# 3_3_5_9_12.net
KiCad netlist of a schematic drawn in EAGLE
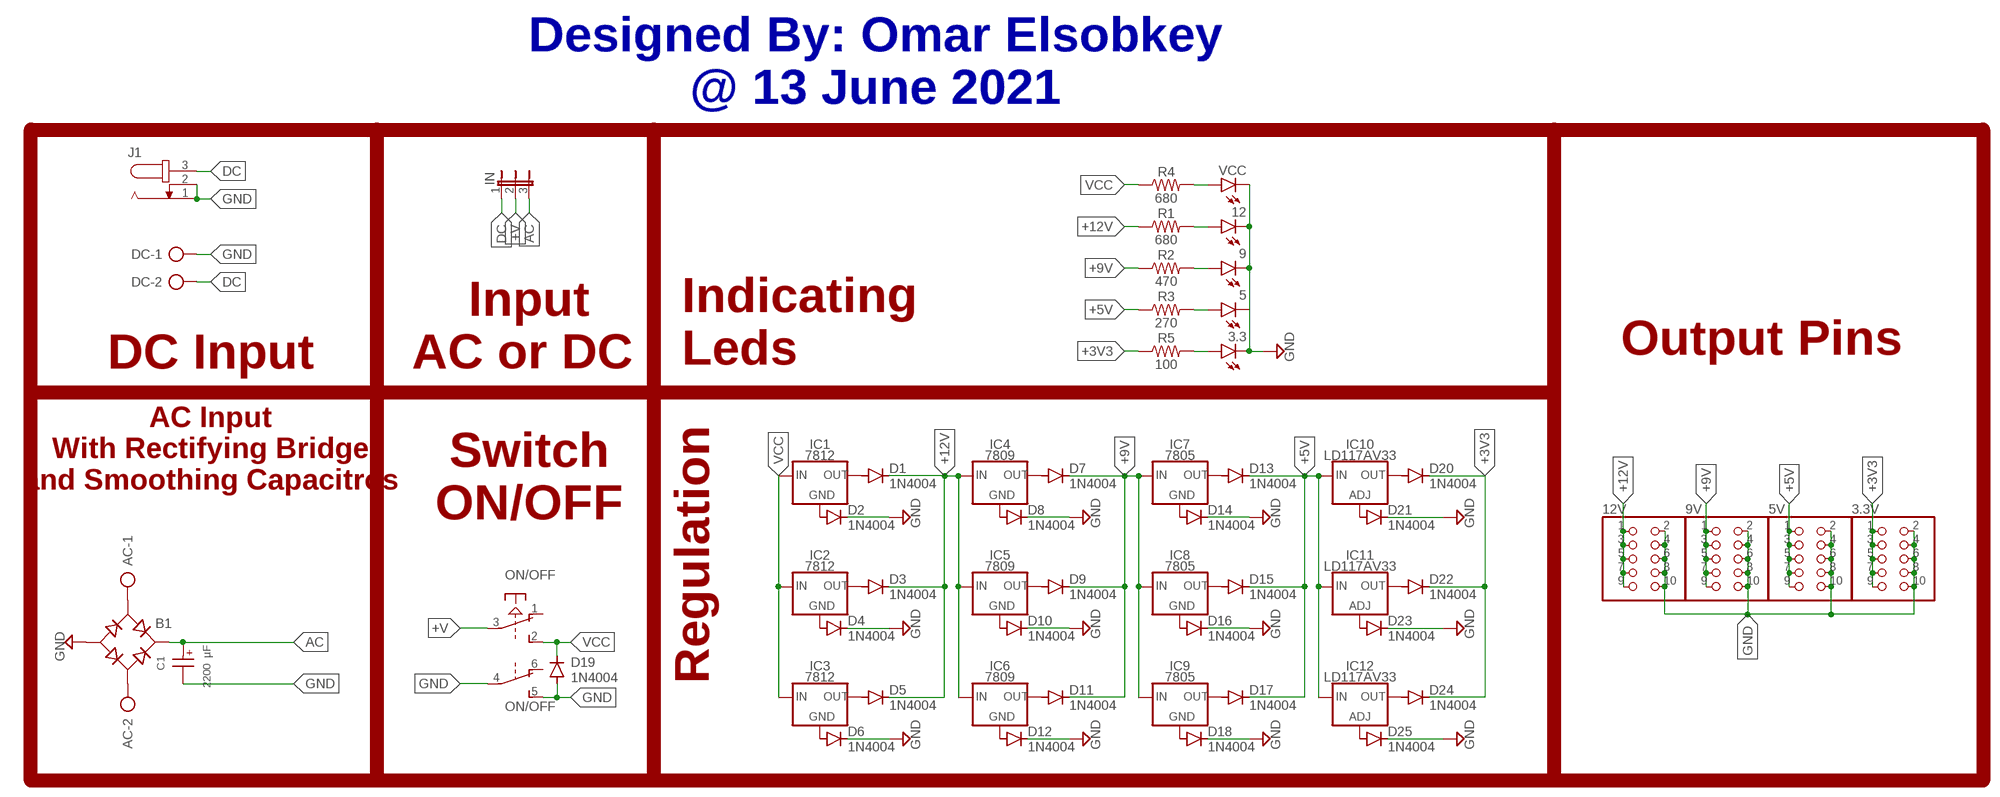
[diagram p0: schematic, sheet 1]

(export (version "E")
  (design (tool "Eeschema 10.0.6"))
  (components
    (comp (ref "3.3")
      (value "LED5MM")
      (footprint "eagle-import:LED5MM")
      (libsource (lib "eagle-import") (part "LED5MM"))
    )
    (comp (ref "3.3V")
      (value "PINHD-2X5")
      (footprint "eagle-import:2X05")
      (libsource (lib "eagle-import") (part "PINHD-2X5"))
    )
    (comp (ref "5")
      (value "LED5MM")
      (footprint "eagle-import:LED5MM")
      (libsource (lib "eagle-import") (part "LED5MM"))
    )
    (comp (ref "5V")
      (value "PINHD-2X5")
      (footprint "eagle-import:2X05")
      (libsource (lib "eagle-import") (part "PINHD-2X5"))
    )
    (comp (ref "9")
      (value "LED5MM")
      (footprint "eagle-import:LED5MM")
      (libsource (lib "eagle-import") (part "LED5MM"))
    )
    (comp (ref "9V")
      (value "PINHD-2X5")
      (footprint "eagle-import:2X05")
      (libsource (lib "eagle-import") (part "PINHD-2X5"))
    )
    (comp (ref "12")
      (value "LED5MM")
      (footprint "eagle-import:LED5MM")
      (libsource (lib "eagle-import") (part "LED5MM"))
    )
    (comp (ref "12V")
      (value "PINHD-2X5")
      (footprint "eagle-import:2X05")
      (libsource (lib "eagle-import") (part "PINHD-2X5"))
    )
    (comp (ref "AC")
      (value "AK500/2-H")
      (footprint "eagle-import:AK500_2-H")
      (libsource (lib "eagle-import") (part "AK500/2-H"))
    )
    (comp (ref "B1")
      (value "RB1A")
      (footprint "eagle-import:RB1A")
      (libsource (lib "eagle-import") (part "RB1A"))
    )
    (comp (ref "C1")
      (value "2200 µF")
      (footprint "eagle-import:WCAP-ATG8_16X25(DXL)")
      (libsource (lib "eagle-import") (part "WCAP-ATG8_16X25_860010580021"))
    )
    (comp (ref "D1")
      (value "1N4004")
      (footprint "eagle-import:DO41-10")
      (libsource (lib "eagle-import") (part "1N4004"))
    )
    (comp (ref "D2")
      (value "1N4004")
      (footprint "eagle-import:DO41-10")
      (libsource (lib "eagle-import") (part "1N4004"))
    )
    (comp (ref "D3")
      (value "1N4004")
      (footprint "eagle-import:DO41-10")
      (libsource (lib "eagle-import") (part "1N4004"))
    )
    (comp (ref "D4")
      (value "1N4004")
      (footprint "eagle-import:DO41-10")
      (libsource (lib "eagle-import") (part "1N4004"))
    )
    (comp (ref "D5")
      (value "1N4004")
      (footprint "eagle-import:DO41-10")
      (libsource (lib "eagle-import") (part "1N4004"))
    )
    (comp (ref "D6")
      (value "1N4004")
      (footprint "eagle-import:DO41-10")
      (libsource (lib "eagle-import") (part "1N4004"))
    )
    (comp (ref "D7")
      (value "1N4004")
      (footprint "eagle-import:DO41-10")
      (libsource (lib "eagle-import") (part "1N4004"))
    )
    (comp (ref "D8")
      (value "1N4004")
      (footprint "eagle-import:DO41-10")
      (libsource (lib "eagle-import") (part "1N4004"))
    )
    (comp (ref "D9")
      (value "1N4004")
      (footprint "eagle-import:DO41-10")
      (libsource (lib "eagle-import") (part "1N4004"))
    )
    (comp (ref "D10")
      (value "1N4004")
      (footprint "eagle-import:DO41-10")
      (libsource (lib "eagle-import") (part "1N4004"))
    )
    (comp (ref "D11")
      (value "1N4004")
      (footprint "eagle-import:DO41-10")
      (libsource (lib "eagle-import") (part "1N4004"))
    )
    (comp (ref "D12")
      (value "1N4004")
      (footprint "eagle-import:DO41-10")
      (libsource (lib "eagle-import") (part "1N4004"))
    )
    (comp (ref "D13")
      (value "1N4004")
      (footprint "eagle-import:DO41-10")
      (libsource (lib "eagle-import") (part "1N4004"))
    )
    (comp (ref "D14")
      (value "1N4004")
      (footprint "eagle-import:DO41-10")
      (libsource (lib "eagle-import") (part "1N4004"))
    )
    (comp (ref "D15")
      (value "1N4004")
      (footprint "eagle-import:DO41-10")
      (libsource (lib "eagle-import") (part "1N4004"))
    )
    (comp (ref "D16")
      (value "1N4004")
      (footprint "eagle-import:DO41-10")
      (libsource (lib "eagle-import") (part "1N4004"))
    )
    (comp (ref "D17")
      (value "1N4004")
      (footprint "eagle-import:DO41-10")
      (libsource (lib "eagle-import") (part "1N4004"))
    )
    (comp (ref "D18")
      (value "1N4004")
      (footprint "eagle-import:DO41-10")
      (libsource (lib "eagle-import") (part "1N4004"))
    )
    (comp (ref "D19")
      (value "1N4004")
      (footprint "eagle-import:DO41-10")
      (libsource (lib "eagle-import") (part "1N4004"))
    )
    (comp (ref "D20")
      (value "1N4004")
      (footprint "eagle-import:DO41-10")
      (libsource (lib "eagle-import") (part "1N4004"))
    )
    (comp (ref "D21")
      (value "1N4004")
      (footprint "eagle-import:DO41-10")
      (libsource (lib "eagle-import") (part "1N4004"))
    )
    (comp (ref "D22")
      (value "1N4004")
      (footprint "eagle-import:DO41-10")
      (libsource (lib "eagle-import") (part "1N4004"))
    )
    (comp (ref "D23")
      (value "1N4004")
      (footprint "eagle-import:DO41-10")
      (libsource (lib "eagle-import") (part "1N4004"))
    )
    (comp (ref "D24")
      (value "1N4004")
      (footprint "eagle-import:DO41-10")
      (libsource (lib "eagle-import") (part "1N4004"))
    )
    (comp (ref "D25")
      (value "1N4004")
      (footprint "eagle-import:DO41-10")
      (libsource (lib "eagle-import") (part "1N4004"))
    )
    (comp (ref "DC")
      (value "AK500/2-H")
      (footprint "eagle-import:AK500_2-H")
      (libsource (lib "eagle-import") (part "AK500/2-H"))
    )
    (comp (ref "IC1")
      (value "7812")
      (footprint "eagle-import:78XXS")
      (libsource (lib "eagle-import") (part "78XXS"))
    )
    (comp (ref "IC2")
      (value "7812")
      (footprint "eagle-import:78XXS")
      (libsource (lib "eagle-import") (part "78XXS"))
    )
    (comp (ref "IC3")
      (value "7812")
      (footprint "eagle-import:78XXS")
      (libsource (lib "eagle-import") (part "78XXS"))
    )
    (comp (ref "IC4")
      (value "7809")
      (footprint "eagle-import:78XXS")
      (libsource (lib "eagle-import") (part "78XXS"))
    )
    (comp (ref "IC5")
      (value "7809")
      (footprint "eagle-import:78XXS")
      (libsource (lib "eagle-import") (part "78XXS"))
    )
    (comp (ref "IC6")
      (value "7809")
      (footprint "eagle-import:78XXS")
      (libsource (lib "eagle-import") (part "78XXS"))
    )
    (comp (ref "IC7")
      (value "7805")
      (footprint "eagle-import:78XXS")
      (libsource (lib "eagle-import") (part "78XXS"))
    )
    (comp (ref "IC8")
      (value "7805")
      (footprint "eagle-import:78XXS")
      (libsource (lib "eagle-import") (part "78XXS"))
    )
    (comp (ref "IC9")
      (value "7805")
      (footprint "eagle-import:78XXS")
      (libsource (lib "eagle-import") (part "78XXS"))
    )
    (comp (ref "IC10")
      (value "LD117AV33")
      (footprint "eagle-import:TO220L1")
      (libsource (lib "eagle-import") (part "LD117A?V33"))
    )
    (comp (ref "IC11")
      (value "LD117AV33")
      (footprint "eagle-import:TO220L1")
      (libsource (lib "eagle-import") (part "LD117A?V33"))
    )
    (comp (ref "IC12")
      (value "LD117AV33")
      (footprint "eagle-import:TO220L1")
      (libsource (lib "eagle-import") (part "LD117A?V33"))
    )
    (comp (ref "IN")
      (value "JP2E")
      (footprint "eagle-import:JP2")
      (libsource (lib "eagle-import") (part "JP2E"))
    )
    (comp (ref "J1")
      (value "JACK-PLUG0")
      (footprint "eagle-import:SPC4077")
      (libsource (lib "eagle-import") (part "JACK-PLUG0"))
    )
    (comp (ref "ON/OFF")
      (value "PVA2R")
      (footprint "eagle-import:PVA2R")
      (libsource (lib "eagle-import") (part "PVA2R"))
    )
    (comp (ref "R1")
      (value "680")
      (footprint "eagle-import:AXIAL-0.3")
      (libsource (lib "eagle-import") (part "RESISTORAXIAL-0.3"))
    )
    (comp (ref "R2")
      (value "470")
      (footprint "eagle-import:AXIAL-0.3")
      (libsource (lib "eagle-import") (part "RESISTORAXIAL-0.3"))
    )
    (comp (ref "R3")
      (value "270")
      (footprint "eagle-import:AXIAL-0.3")
      (libsource (lib "eagle-import") (part "RESISTORAXIAL-0.3"))
    )
    (comp (ref "R4")
      (value "680")
      (footprint "eagle-import:AXIAL-0.3")
      (libsource (lib "eagle-import") (part "RESISTORAXIAL-0.3"))
    )
    (comp (ref "R5")
      (value "100")
      (footprint "eagle-import:AXIAL-0.3")
      (libsource (lib "eagle-import") (part "RESISTORAXIAL-0.3"))
    )
    (comp (ref "VCC")
      (value "LED5MM")
      (footprint "eagle-import:LED5MM")
      (libsource (lib "eagle-import") (part "LED5MM"))
    )
  )
  (nets
    (net (code "1") (name "+3V3") (class "Default")
      (node (ref "3.3V") (pin "1") (pinfunction "1_1") (pintype "passive"))
      (node (ref "3.3V") (pin "3") (pinfunction "3_3") (pintype "passive"))
      (node (ref "3.3V") (pin "5") (pinfunction "5_5") (pintype "passive"))
      (node (ref "3.3V") (pin "7") (pinfunction "7_7") (pintype "passive"))
      (node (ref "3.3V") (pin "9") (pinfunction "9_9") (pintype "passive"))
      (node (ref "D20") (pin "C") (pinfunction "C_C") (pintype "passive"))
      (node (ref "D22") (pin "C") (pinfunction "C_C") (pintype "passive"))
      (node (ref "D24") (pin "C") (pinfunction "C_C") (pintype "passive"))
      (node (ref "R5") (pin "P$1") (pinfunction "1_P$1") (pintype "passive"))
    )
    (net (code "2") (name "+5V") (class "Default")
      (node (ref "5V") (pin "1") (pinfunction "1_1") (pintype "passive"))
      (node (ref "5V") (pin "3") (pinfunction "3_3") (pintype "passive"))
      (node (ref "5V") (pin "5") (pinfunction "5_5") (pintype "passive"))
      (node (ref "5V") (pin "7") (pinfunction "7_7") (pintype "passive"))
      (node (ref "5V") (pin "9") (pinfunction "9_9") (pintype "passive"))
      (node (ref "D13") (pin "C") (pinfunction "C_C") (pintype "passive"))
      (node (ref "D15") (pin "C") (pinfunction "C_C") (pintype "passive"))
      (node (ref "D17") (pin "C") (pinfunction "C_C") (pintype "passive"))
      (node (ref "IC10") (pin "3") (pinfunction "IN_3") (pintype "input"))
      (node (ref "IC11") (pin "3") (pinfunction "IN_3") (pintype "input"))
      (node (ref "IC12") (pin "3") (pinfunction "IN_3") (pintype "input"))
      (node (ref "R3") (pin "P$1") (pinfunction "1_P$1") (pintype "passive"))
    )
    (net (code "3") (name "+9V") (class "Default")
      (node (ref "9V") (pin "1") (pinfunction "1_1") (pintype "passive"))
      (node (ref "9V") (pin "3") (pinfunction "3_3") (pintype "passive"))
      (node (ref "9V") (pin "5") (pinfunction "5_5") (pintype "passive"))
      (node (ref "9V") (pin "7") (pinfunction "7_7") (pintype "passive"))
      (node (ref "9V") (pin "9") (pinfunction "9_9") (pintype "passive"))
      (node (ref "D11") (pin "C") (pinfunction "C_C") (pintype "passive"))
      (node (ref "D7") (pin "C") (pinfunction "C_C") (pintype "passive"))
      (node (ref "D9") (pin "C") (pinfunction "C_C") (pintype "passive"))
      (node (ref "IC7") (pin "IN") (pinfunction "IN_IN") (pintype "input"))
      (node (ref "IC8") (pin "IN") (pinfunction "IN_IN") (pintype "input"))
      (node (ref "IC9") (pin "IN") (pinfunction "IN_IN") (pintype "input"))
      (node (ref "R2") (pin "P$1") (pinfunction "1_P$1") (pintype "passive"))
    )
    (net (code "4") (name "+12V") (class "Default")
      (node (ref "12V") (pin "1") (pinfunction "1_1") (pintype "passive"))
      (node (ref "12V") (pin "3") (pinfunction "3_3") (pintype "passive"))
      (node (ref "12V") (pin "5") (pinfunction "5_5") (pintype "passive"))
      (node (ref "12V") (pin "7") (pinfunction "7_7") (pintype "passive"))
      (node (ref "12V") (pin "9") (pinfunction "9_9") (pintype "passive"))
      (node (ref "D1") (pin "C") (pinfunction "C_C") (pintype "passive"))
      (node (ref "D3") (pin "C") (pinfunction "C_C") (pintype "passive"))
      (node (ref "D5") (pin "C") (pinfunction "C_C") (pintype "passive"))
      (node (ref "IC4") (pin "IN") (pinfunction "IN_IN") (pintype "input"))
      (node (ref "IC5") (pin "IN") (pinfunction "IN_IN") (pintype "input"))
      (node (ref "IC6") (pin "IN") (pinfunction "IN_IN") (pintype "input"))
      (node (ref "R1") (pin "P$1") (pinfunction "1_P$1") (pintype "passive"))
    )
    (net (code "5") (name "+V") (class "Default")
      (node (ref "IN") (pin "2") (pinfunction "2_2") (pintype "passive"))
      (node (ref "ON/OFF") (pin "3") (pinfunction "P_3") (pintype "passive"))
    )
    (net (code "6") (name "AC") (class "Default")
      (node (ref "B1") (pin "+") (pinfunction "+_+") (pintype "passive"))
      (node (ref "C1") (pin "1") (pinfunction "+_1") (pintype "passive"))
      (node (ref "IN") (pin "3") (pinfunction "3_3") (pintype "passive"))
    )
    (net (code "7") (name "DC") (class "Default")
      (node (ref "DC") (pin "2") (pinfunction "KL_2") (pintype "passive"))
      (node (ref "IN") (pin "1") (pinfunction "1_1") (pintype "passive"))
      (node (ref "J1") (pin "3") (pinfunction "3_3") (pintype "passive"))
    )
    (net (code "8") (name "GND") (class "Default")
      (node (ref "12") (pin "K") (pinfunction "C_K") (pintype "passive"))
      (node (ref "12V") (pin "10") (pinfunction "10_10") (pintype "passive"))
      (node (ref "12V") (pin "2") (pinfunction "2_2") (pintype "passive"))
      (node (ref "12V") (pin "4") (pinfunction "4_4") (pintype "passive"))
      (node (ref "12V") (pin "6") (pinfunction "6_6") (pintype "passive"))
      (node (ref "12V") (pin "8") (pinfunction "8_8") (pintype "passive"))
      (node (ref "3.3") (pin "K") (pinfunction "C_K") (pintype "passive"))
      (node (ref "3.3V") (pin "10") (pinfunction "10_10") (pintype "passive"))
      (node (ref "3.3V") (pin "2") (pinfunction "2_2") (pintype "passive"))
      (node (ref "3.3V") (pin "4") (pinfunction "4_4") (pintype "passive"))
      (node (ref "3.3V") (pin "6") (pinfunction "6_6") (pintype "passive"))
      (node (ref "3.3V") (pin "8") (pinfunction "8_8") (pintype "passive"))
      (node (ref "5") (pin "K") (pinfunction "C_K") (pintype "passive"))
      (node (ref "5V") (pin "10") (pinfunction "10_10") (pintype "passive"))
      (node (ref "5V") (pin "2") (pinfunction "2_2") (pintype "passive"))
      (node (ref "5V") (pin "4") (pinfunction "4_4") (pintype "passive"))
      (node (ref "5V") (pin "6") (pinfunction "6_6") (pintype "passive"))
      (node (ref "5V") (pin "8") (pinfunction "8_8") (pintype "passive"))
      (node (ref "9") (pin "K") (pinfunction "C_K") (pintype "passive"))
      (node (ref "9V") (pin "10") (pinfunction "10_10") (pintype "passive"))
      (node (ref "9V") (pin "2") (pinfunction "2_2") (pintype "passive"))
      (node (ref "9V") (pin "4") (pinfunction "4_4") (pintype "passive"))
      (node (ref "9V") (pin "6") (pinfunction "6_6") (pintype "passive"))
      (node (ref "9V") (pin "8") (pinfunction "8_8") (pintype "passive"))
      (node (ref "B1") (pin "-") (pinfunction "-_-") (pintype "passive"))
      (node (ref "C1") (pin "2") (pinfunction "-_2") (pintype "passive"))
      (node (ref "D10") (pin "C") (pinfunction "C_C") (pintype "passive"))
      (node (ref "D12") (pin "C") (pinfunction "C_C") (pintype "passive"))
      (node (ref "D14") (pin "C") (pinfunction "C_C") (pintype "passive"))
      (node (ref "D16") (pin "C") (pinfunction "C_C") (pintype "passive"))
      (node (ref "D18") (pin "C") (pinfunction "C_C") (pintype "passive"))
      (node (ref "D19") (pin "A") (pinfunction "A_A") (pintype "passive"))
      (node (ref "D2") (pin "C") (pinfunction "C_C") (pintype "passive"))
      (node (ref "D21") (pin "C") (pinfunction "C_C") (pintype "passive"))
      (node (ref "D23") (pin "C") (pinfunction "C_C") (pintype "passive"))
      (node (ref "D25") (pin "C") (pinfunction "C_C") (pintype "passive"))
      (node (ref "D4") (pin "C") (pinfunction "C_C") (pintype "passive"))
      (node (ref "D6") (pin "C") (pinfunction "C_C") (pintype "passive"))
      (node (ref "D8") (pin "C") (pinfunction "C_C") (pintype "passive"))
      (node (ref "DC") (pin "1") (pinfunction "KL_1") (pintype "passive"))
      (node (ref "J1") (pin "1") (pinfunction "1_1") (pintype "passive"))
      (node (ref "J1") (pin "2") (pinfunction "2_2") (pintype "passive"))
      (node (ref "ON/OFF") (pin "4") (pinfunction "P_4") (pintype "passive"))
      (node (ref "ON/OFF") (pin "5") (pinfunction "S_5") (pintype "passive"))
      (node (ref "VCC") (pin "K") (pinfunction "C_K") (pintype "passive"))
    )
    (net (code "9") (name "Net-(ACA-KL)") (class "Default")
      (node (ref "AC") (pin "1") (pinfunction "KL_1") (pintype "passive"))
      (node (ref "B1") (pin "AC1") (pinfunction "AC1_AC1") (pintype "passive"))
    )
    (net (code "10") (name "Net-(ACB-KL)") (class "Default")
      (node (ref "AC") (pin "2") (pinfunction "KL_2") (pintype "passive"))
      (node (ref "B1") (pin "AC2") (pinfunction "AC2_AC2") (pintype "passive"))
    )
    (net (code "11") (name "Net-(D1-PadA)") (class "Default")
      (node (ref "D1") (pin "A") (pinfunction "A_A") (pintype "passive"))
      (node (ref "IC1") (pin "OUT") (pinfunction "OUT_OUT") (pintype "passive"))
    )
    (net (code "12") (name "Net-(D2-PadA)") (class "Default")
      (node (ref "D2") (pin "A") (pinfunction "A_A") (pintype "passive"))
      (node (ref "IC1") (pin "GND") (pinfunction "GND_GND") (pintype "input"))
    )
    (net (code "13") (name "Net-(D3-PadA)") (class "Default")
      (node (ref "D3") (pin "A") (pinfunction "A_A") (pintype "passive"))
      (node (ref "IC2") (pin "OUT") (pinfunction "OUT_OUT") (pintype "passive"))
    )
    (net (code "14") (name "Net-(D4-PadA)") (class "Default")
      (node (ref "D4") (pin "A") (pinfunction "A_A") (pintype "passive"))
      (node (ref "IC2") (pin "GND") (pinfunction "GND_GND") (pintype "input"))
    )
    (net (code "15") (name "Net-(D5-PadA)") (class "Default")
      (node (ref "D5") (pin "A") (pinfunction "A_A") (pintype "passive"))
      (node (ref "IC3") (pin "OUT") (pinfunction "OUT_OUT") (pintype "passive"))
    )
    (net (code "16") (name "Net-(D6-PadA)") (class "Default")
      (node (ref "D6") (pin "A") (pinfunction "A_A") (pintype "passive"))
      (node (ref "IC3") (pin "GND") (pinfunction "GND_GND") (pintype "input"))
    )
    (net (code "17") (name "Net-(D7-PadA)") (class "Default")
      (node (ref "D7") (pin "A") (pinfunction "A_A") (pintype "passive"))
      (node (ref "IC4") (pin "OUT") (pinfunction "OUT_OUT") (pintype "passive"))
    )
    (net (code "18") (name "Net-(D8-PadA)") (class "Default")
      (node (ref "D8") (pin "A") (pinfunction "A_A") (pintype "passive"))
      (node (ref "IC4") (pin "GND") (pinfunction "GND_GND") (pintype "input"))
    )
    (net (code "19") (name "Net-(D9-PadA)") (class "Default")
      (node (ref "D9") (pin "A") (pinfunction "A_A") (pintype "passive"))
      (node (ref "IC5") (pin "OUT") (pinfunction "OUT_OUT") (pintype "passive"))
    )
    (net (code "20") (name "Net-(D10-PadA)") (class "Default")
      (node (ref "D10") (pin "A") (pinfunction "A_A") (pintype "passive"))
      (node (ref "IC5") (pin "GND") (pinfunction "GND_GND") (pintype "input"))
    )
    (net (code "21") (name "Net-(D11-PadA)") (class "Default")
      (node (ref "D11") (pin "A") (pinfunction "A_A") (pintype "passive"))
      (node (ref "IC6") (pin "OUT") (pinfunction "OUT_OUT") (pintype "passive"))
    )
    (net (code "22") (name "Net-(D12-PadA)") (class "Default")
      (node (ref "D12") (pin "A") (pinfunction "A_A") (pintype "passive"))
      (node (ref "IC6") (pin "GND") (pinfunction "GND_GND") (pintype "input"))
    )
    (net (code "23") (name "Net-(D13-PadA)") (class "Default")
      (node (ref "D13") (pin "A") (pinfunction "A_A") (pintype "passive"))
      (node (ref "IC7") (pin "OUT") (pinfunction "OUT_OUT") (pintype "passive"))
    )
    (net (code "24") (name "Net-(D14-PadA)") (class "Default")
      (node (ref "D14") (pin "A") (pinfunction "A_A") (pintype "passive"))
      (node (ref "IC7") (pin "GND") (pinfunction "GND_GND") (pintype "input"))
    )
    (net (code "25") (name "Net-(D15-PadA)") (class "Default")
      (node (ref "D15") (pin "A") (pinfunction "A_A") (pintype "passive"))
      (node (ref "IC8") (pin "OUT") (pinfunction "OUT_OUT") (pintype "passive"))
    )
    (net (code "26") (name "Net-(D16-PadA)") (class "Default")
      (node (ref "D16") (pin "A") (pinfunction "A_A") (pintype "passive"))
      (node (ref "IC8") (pin "GND") (pinfunction "GND_GND") (pintype "input"))
    )
    (net (code "27") (name "Net-(D17-PadA)") (class "Default")
      (node (ref "D17") (pin "A") (pinfunction "A_A") (pintype "passive"))
      (node (ref "IC9") (pin "OUT") (pinfunction "OUT_OUT") (pintype "passive"))
    )
    (net (code "28") (name "Net-(D18-PadA)") (class "Default")
      (node (ref "D18") (pin "A") (pinfunction "A_A") (pintype "passive"))
      (node (ref "IC9") (pin "GND") (pinfunction "GND_GND") (pintype "input"))
    )
    (net (code "29") (name "Net-(IC10-ADJ)") (class "Default")
      (node (ref "D21") (pin "A") (pinfunction "A_A") (pintype "passive"))
      (node (ref "IC10") (pin "1") (pinfunction "ADJ_1") (pintype "input"))
    )
    (net (code "30") (name "Net-(IC10-OUT)") (class "Default")
      (node (ref "D20") (pin "A") (pinfunction "A_A") (pintype "passive"))
      (node (ref "IC10") (pin "2") (pinfunction "OUT_2") (pintype "passive"))
    )
    (net (code "31") (name "Net-(IC11-ADJ)") (class "Default")
      (node (ref "D23") (pin "A") (pinfunction "A_A") (pintype "passive"))
      (node (ref "IC11") (pin "1") (pinfunction "ADJ_1") (pintype "input"))
    )
    (net (code "32") (name "Net-(IC11-OUT)") (class "Default")
      (node (ref "D22") (pin "A") (pinfunction "A_A") (pintype "passive"))
      (node (ref "IC11") (pin "2") (pinfunction "OUT_2") (pintype "passive"))
    )
    (net (code "33") (name "Net-(IC12-ADJ)") (class "Default")
      (node (ref "D25") (pin "A") (pinfunction "A_A") (pintype "passive"))
      (node (ref "IC12") (pin "1") (pinfunction "ADJ_1") (pintype "input"))
    )
    (net (code "34") (name "Net-(IC12-OUT)") (class "Default")
      (node (ref "D24") (pin "A") (pinfunction "A_A") (pintype "passive"))
      (node (ref "IC12") (pin "2") (pinfunction "OUT_2") (pintype "passive"))
    )
    (net (code "35") (name "Net-(R1-2)") (class "Default")
      (node (ref "12") (pin "A") (pinfunction "A_A") (pintype "passive"))
      (node (ref "R1") (pin "P$2") (pinfunction "2_P$2") (pintype "passive"))
    )
    (net (code "36") (name "Net-(R2-2)") (class "Default")
      (node (ref "9") (pin "A") (pinfunction "A_A") (pintype "passive"))
      (node (ref "R2") (pin "P$2") (pinfunction "2_P$2") (pintype "passive"))
    )
    (net (code "37") (name "Net-(R3-2)") (class "Default")
      (node (ref "5") (pin "A") (pinfunction "A_A") (pintype "passive"))
      (node (ref "R3") (pin "P$2") (pinfunction "2_P$2") (pintype "passive"))
    )
    (net (code "38") (name "Net-(R4-2)") (class "Default")
      (node (ref "R4") (pin "P$2") (pinfunction "2_P$2") (pintype "passive"))
      (node (ref "VCC") (pin "A") (pinfunction "A_A") (pintype "passive"))
    )
    (net (code "39") (name "Net-(R5-2)") (class "Default")
      (node (ref "3.3") (pin "A") (pinfunction "A_A") (pintype "passive"))
      (node (ref "R5") (pin "P$2") (pinfunction "2_P$2") (pintype "passive"))
    )
    (net (code "40") (name "VCC") (class "Default")
      (node (ref "D19") (pin "C") (pinfunction "C_C") (pintype "passive"))
      (node (ref "IC1") (pin "IN") (pinfunction "IN_IN") (pintype "input"))
      (node (ref "IC2") (pin "IN") (pinfunction "IN_IN") (pintype "input"))
      (node (ref "IC3") (pin "IN") (pinfunction "IN_IN") (pintype "input"))
      (node (ref "ON/OFF") (pin "2") (pinfunction "S_2") (pintype "passive"))
      (node (ref "R4") (pin "P$1") (pinfunction "1_P$1") (pintype "passive"))
    )
    (net (code "41") (name "unconnected-(ON/OFFA-O-Pad1)") (class "Default")
      (node (ref "ON/OFF") (pin "1") (pinfunction "O_1") (pintype "passive"))
    )
    (net (code "42") (name "unconnected-(ON/OFFB-O-Pad6)") (class "Default")
      (node (ref "ON/OFF") (pin "6") (pinfunction "O_6") (pintype "passive"))
    )
  )
)
